# sensors.net
KiCad netlist of a schematic drawn in Altium Designer
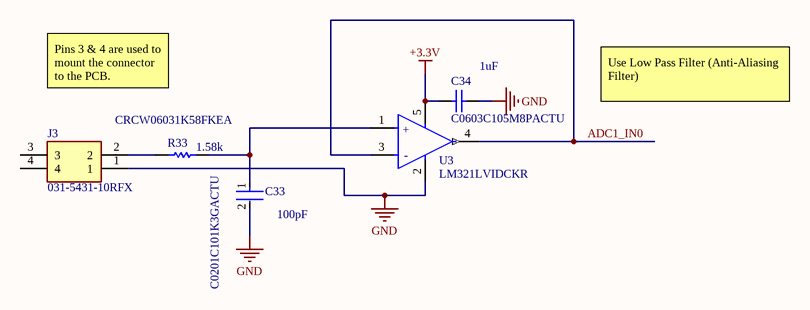
[diagram p0: sensors.SchDoc]

(export (version "E")
  (design (tool "Eeschema 10.0.6"))
  (components
    (comp (ref "C33")
      (value "C0201C101K3GACTU")
      (footprint "FP-C0201-AB-MFG")
      (description "CAP CER 100PF 25V 5% NP0 0201")
      (fields
        (field (name "OCTOPART") "https://octopart.com/c0201c101k3gactu-kemet-17054818")
        (field (name "TOLERANCE") "0.1")
      )
      (libsource (lib "Altium Content Vault") (part "11868f565c42a9108669ba33697ecf6"))
    )
    (comp (ref "C34")
      (value "C0603C105M8PACTU")
      (footprint "CAPC1608X90X35LL15T15")
      (fields (field (name "MANUFACTURER") "Kemet"))
      (libsource (lib "Altium Content Vault") (part "CAP"))
    )
    (comp (ref "J3")
      (value "031-5431-10RFX")
      (footprint "031543110RFX:031543110RFX")
      (description "Amphenol BNC Series Right Angle 50 Through Hole BNC Connector, jack, Nickel, Solder Termination")
      (fields (field (name "MOUSER PART NUMBER") "523-31-5431-10RFX"))
      (libsource (lib "031-5431-10RFX") (part "031-5431-10RFX"))
    )
    (comp (ref "R33")
      (value "CRCW06031K58FKEA")
      (footprint "RESC1609X50X30NL10T20")
      (fields (field (name "MANUFACTURER") "Vishay Dale"))
      (libsource (lib "Altium Content Vault") (part "RES"))
    )
    (comp (ref "U3")
      (value "LM321LVIDCKR")
      (footprint "FP-DCK0005A-IPC_B")
      (description "IC OPAMP GP 1 CIRCUIT SC70-5")
      (libsource (lib "Altium Content Vault") (part "471d8b929410cd356ad4b122f572ce5"))
    )
  )
  (nets
    (net (code "1") (name "+3.3V") (class "Default")
      (node (ref "C34") (pin "2") (pinfunction "2_2") (pintype "passive"))
      (node (ref "U3") (pin "5") (pinfunction "V+_5") (pintype "power_in"))
    )
    (net (code "2") (name "/ADC1_IN0") (class "Default")
      (node (ref "U3") (pin "3") (pinfunction "IN-_3") (pintype "tri_state"))
      (node (ref "U3") (pin "4") (pinfunction "OUT_4") (pintype "output"))
    )
    (net (code "3") (name "GND") (class "Default")
      (node (ref "C33") (pin "2") (pinfunction "2_2") (pintype "passive"))
      (node (ref "C34") (pin "1") (pinfunction "1_1") (pintype "passive"))
      (node (ref "J3") (pin "1") (pinfunction "1_1") (pintype "passive"))
      (node (ref "U3") (pin "2") (pinfunction "V-_2") (pintype "power_in"))
    )
    (net (code "4") (name "Net-(J3-Pad2)") (class "Default")
      (node (ref "J3") (pin "2") (pinfunction "2_2") (pintype "passive"))
      (node (ref "R33") (pin "1") (pinfunction "1_1") (pintype "passive"))
    )
    (net (code "5") (name "Net-(U3-IN+)") (class "Default")
      (node (ref "C33") (pin "1") (pinfunction "1_1") (pintype "passive"))
      (node (ref "R33") (pin "2") (pinfunction "2_2") (pintype "passive"))
      (node (ref "U3") (pin "1") (pinfunction "IN+_1") (pintype "tri_state"))
    )
    (net (code "6") (name "unconnected-(J3-Pad3)") (class "Default")
      (node (ref "J3") (pin "3") (pinfunction "3_3") (pintype "passive"))
    )
    (net (code "7") (name "unconnected-(J3-Pad4)") (class "Default")
      (node (ref "J3") (pin "4") (pinfunction "4_4") (pintype "passive"))
    )
  )
)
